# BRCM_V1.net
KiCad netlist of a schematic drawn in Altium Designer
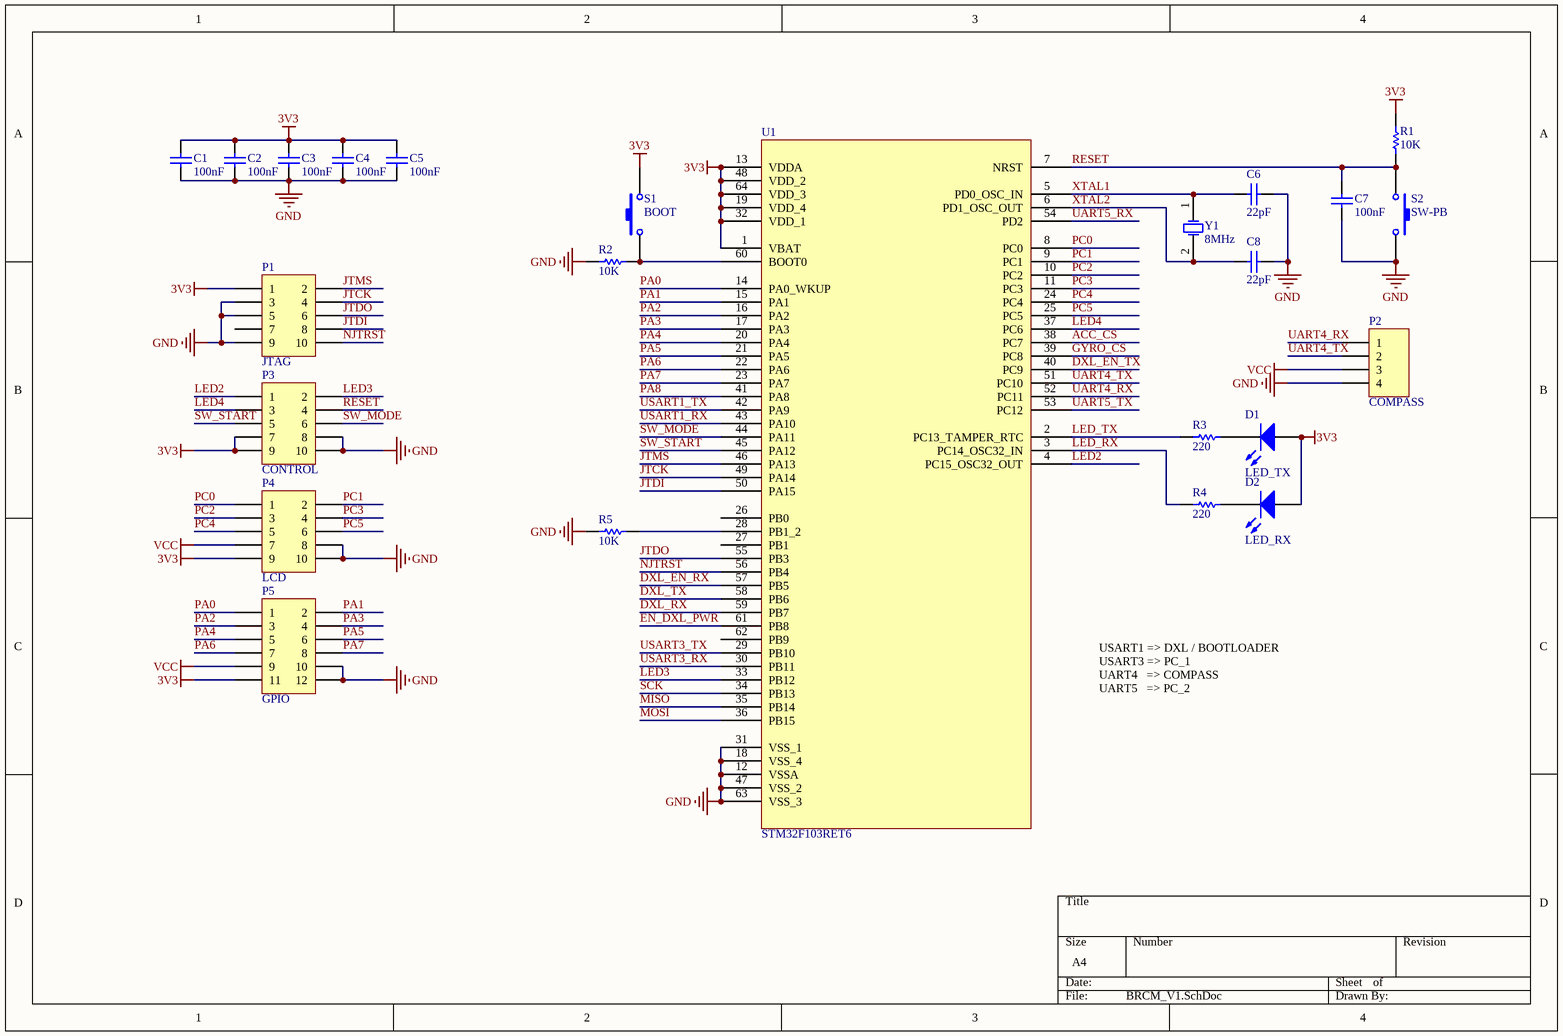
[diagram p0: BRCM_V1.SchDoc]

(export (version "E")
  (design (tool "Eeschema 10.0.6"))
  (components
    (comp (ref "C1")
      (value "100nF")
      (footprint "0603-CAP")
      (description "Capacitor")
      (fields (field (name "PUBLISHER") "Altium Limited"))
      (libsource (lib "BarelangRobotics") (part "Cap"))
    )
    (comp (ref "C2")
      (value "100nF")
      (footprint "0603-CAP")
      (description "Capacitor")
      (fields (field (name "PUBLISHER") "Altium Limited"))
      (libsource (lib "BarelangRobotics") (part "Cap"))
    )
    (comp (ref "C3")
      (value "100nF")
      (footprint "0603-CAP")
      (description "Capacitor")
      (fields (field (name "PUBLISHER") "Altium Limited"))
      (libsource (lib "BarelangRobotics") (part "Cap"))
    )
    (comp (ref "C4")
      (value "100nF")
      (footprint "0603-CAP")
      (description "Capacitor")
      (fields (field (name "PUBLISHER") "Altium Limited"))
      (libsource (lib "BarelangRobotics") (part "Cap"))
    )
    (comp (ref "C5")
      (value "100nF")
      (footprint "0603-CAP")
      (description "Capacitor")
      (fields (field (name "PUBLISHER") "Altium Limited"))
      (libsource (lib "BarelangRobotics") (part "Cap"))
    )
    (comp (ref "C6")
      (value "22pF")
      (footprint "0603-CAP")
      (description "Capacitor")
      (fields (field (name "PUBLISHER") "Altium Limited"))
      (libsource (lib "BarelangRobotics") (part "Cap"))
    )
    (comp (ref "C7")
      (value "100nF")
      (footprint "0603-CAP")
      (description "Capacitor")
      (fields (field (name "PUBLISHER") "Altium Limited"))
      (libsource (lib "BarelangRobotics") (part "Cap"))
    )
    (comp (ref "C8")
      (value "22pF")
      (footprint "0603-CAP")
      (description "Capacitor")
      (fields (field (name "PUBLISHER") "Altium Limited"))
      (libsource (lib "BarelangRobotics") (part "Cap"))
    )
    (comp (ref "D1")
      (value "LED_TX")
      (footprint "CHIPLED_0603")
      (description "Typical INFRARED GaAs LED")
      (fields (field (name "PUBLISHER") "Altium Limited"))
      (libsource (lib "BarelangRobotics") (part "LED"))
    )
    (comp (ref "D2")
      (value "LED_RX")
      (footprint "CHIPLED_0603")
      (description "Typical INFRARED GaAs LED")
      (fields (field (name "PUBLISHER") "Altium Limited"))
      (libsource (lib "BarelangRobotics") (part "LED"))
    )
    (comp (ref "P1")
      (value "JTAG")
      (footprint "HDR2X5")
      (description "Header, 5-Pin, Dual row")
      (fields (field (name "PUBLISHER") "Altium Limited"))
      (libsource (lib "BarelangRobotics") (part "Header 5X2"))
    )
    (comp (ref "P2")
      (value "COMPASS")
      (footprint "HDR1X4")
      (description "Header, 4-Pin")
      (fields (field (name "PUBLISHER") "Altium Limited"))
      (libsource (lib "BarelangRobotics") (part "Header 4"))
    )
    (comp (ref "P3")
      (value "CONTROL")
      (footprint "HDR2X5")
      (description "Header, 5-Pin, Dual row")
      (fields (field (name "PUBLISHER") "Altium Limited"))
      (libsource (lib "BarelangRobotics") (part "Header 5X2"))
    )
    (comp (ref "P4")
      (value "LCD")
      (footprint "HDR2X5")
      (description "Header, 5-Pin, Dual row")
      (fields (field (name "PUBLISHER") "Altium Limited"))
      (libsource (lib "BarelangRobotics") (part "Header 5X2"))
    )
    (comp (ref "P5")
      (value "GPIO")
      (footprint "HDR2X6")
      (description "Header, 6-Pin, Dual row")
      (fields (field (name "PUBLISHER") "Altium Limited"))
      (libsource (lib "BarelangRobotics") (part "Header 6X2"))
    )
    (comp (ref "R1")
      (value "10K")
      (footprint "0603-RES")
      (description "Resistor")
      (fields (field (name "PUBLISHER") "Altium Limited"))
      (libsource (lib "BarelangRobotics") (part "Res"))
    )
    (comp (ref "R2")
      (value "10K")
      (footprint "0603-RES")
      (description "Resistor")
      (fields (field (name "PUBLISHER") "Altium Limited"))
      (libsource (lib "BarelangRobotics") (part "Res"))
    )
    (comp (ref "R3")
      (value "220")
      (footprint "0603-RES")
      (description "Resistor")
      (fields (field (name "PUBLISHER") "Altium Limited"))
      (libsource (lib "BarelangRobotics") (part "Res"))
    )
    (comp (ref "R4")
      (value "220")
      (footprint "0603-RES")
      (description "Resistor")
      (fields (field (name "PUBLISHER") "Altium Limited"))
      (libsource (lib "BarelangRobotics") (part "Res"))
    )
    (comp (ref "R5")
      (value "10K")
      (footprint "0603-RES")
      (description "Resistor")
      (fields (field (name "PUBLISHER") "Altium Limited"))
      (libsource (lib "BarelangRobotics") (part "Res"))
    )
    (comp (ref "S1")
      (value "BOOT")
      (footprint "TACTILE-SWITCH-SMD")
      (description "Switch")
      (fields (field (name "PUBLISHER") "Altium Limited"))
      (libsource (lib "BarelangRobotics") (part "SW-PB"))
    )
    (comp (ref "S2")
      (value "SW-PB")
      (footprint "TACTILE-SWITCH-SMD")
      (description "Switch")
      (fields (field (name "PUBLISHER") "Altium Limited"))
      (libsource (lib "BarelangRobotics") (part "SW-PB"))
    )
    (comp (ref "U1")
      (value "STM32F103RET6")
      (footprint "QFP-64N")
      (libsource (lib "BarelangRobotics") (part "STM32F103RET6"))
    )
    (comp (ref "Y1")
      (value "8MHz")
      (footprint "HC49UP")
      (description "Crystal Oscillator")
      (fields (field (name "PUBLISHER") "Altium Limited"))
      (libsource (lib "BarelangRobotics") (part "XTAL"))
    )
  )
  (nets
    (net (code "1") (name "/ACC_CS") (class "Default")
      (node (ref "U1") (pin "38") (pinfunction "PC7_38") (pintype "passive"))
    )
    (net (code "2") (name "/DXL_EN_RX") (class "Default")
      (node (ref "U1") (pin "57") (pinfunction "PB5_57") (pintype "passive"))
    )
    (net (code "3") (name "/DXL_EN_TX") (class "Default")
      (node (ref "U1") (pin "40") (pinfunction "PC9_40") (pintype "passive"))
    )
    (net (code "4") (name "/DXL_RX") (class "Default")
      (node (ref "U1") (pin "59") (pinfunction "PB7_59") (pintype "passive"))
    )
    (net (code "5") (name "/DXL_TX") (class "Default")
      (node (ref "U1") (pin "58") (pinfunction "PB6_58") (pintype "passive"))
    )
    (net (code "6") (name "/EN_DXL_PWR") (class "Default")
      (node (ref "U1") (pin "61") (pinfunction "PB8_61") (pintype "passive"))
    )
    (net (code "7") (name "/GYRO_CS") (class "Default")
      (node (ref "U1") (pin "39") (pinfunction "PC8_39") (pintype "passive"))
    )
    (net (code "8") (name "/JTCK") (class "Default")
      (node (ref "P1") (pin "4") (pinfunction "4_4") (pintype "passive"))
      (node (ref "U1") (pin "49") (pinfunction "PA14_49") (pintype "passive"))
    )
    (net (code "9") (name "/JTDI") (class "Default")
      (node (ref "P1") (pin "8") (pinfunction "8_8") (pintype "passive"))
      (node (ref "U1") (pin "50") (pinfunction "PA15_50") (pintype "passive"))
    )
    (net (code "10") (name "/JTDO") (class "Default")
      (node (ref "P1") (pin "6") (pinfunction "6_6") (pintype "passive"))
      (node (ref "U1") (pin "55") (pinfunction "PB3_55") (pintype "passive"))
    )
    (net (code "11") (name "/JTMS") (class "Default")
      (node (ref "P1") (pin "2") (pinfunction "2_2") (pintype "passive"))
      (node (ref "U1") (pin "46") (pinfunction "PA13_46") (pintype "passive"))
    )
    (net (code "12") (name "/LED2") (class "Default")
      (node (ref "P3") (pin "1") (pinfunction "1_1") (pintype "passive"))
      (node (ref "U1") (pin "4") (pinfunction "PC15_OSC32_OUT_4") (pintype "passive"))
    )
    (net (code "13") (name "/LED3") (class "Default")
      (node (ref "P3") (pin "2") (pinfunction "2_2") (pintype "passive"))
      (node (ref "U1") (pin "33") (pinfunction "PB12_33") (pintype "passive"))
    )
    (net (code "14") (name "/LED4") (class "Default")
      (node (ref "P3") (pin "3") (pinfunction "3_3") (pintype "passive"))
      (node (ref "U1") (pin "37") (pinfunction "PC6_37") (pintype "passive"))
    )
    (net (code "15") (name "/LED_RX") (class "Default")
      (node (ref "R4") (pin "1") (pinfunction "1_1") (pintype "passive"))
      (node (ref "U1") (pin "3") (pinfunction "PC14_OSC32_IN_3") (pintype "passive"))
    )
    (net (code "16") (name "/LED_TX") (class "Default")
      (node (ref "R3") (pin "1") (pinfunction "1_1") (pintype "passive"))
      (node (ref "U1") (pin "2") (pinfunction "PC13_TAMPER_RTC_2") (pintype "passive"))
    )
    (net (code "17") (name "/MISO") (class "Default")
      (node (ref "U1") (pin "35") (pinfunction "PB14_35") (pintype "passive"))
    )
    (net (code "18") (name "/MOSI") (class "Default")
      (node (ref "U1") (pin "36") (pinfunction "PB15_36") (pintype "passive"))
    )
    (net (code "19") (name "/NJTRST") (class "Default")
      (node (ref "P1") (pin "10") (pinfunction "10_10") (pintype "passive"))
      (node (ref "U1") (pin "56") (pinfunction "PB4_56") (pintype "passive"))
    )
    (net (code "20") (name "/PA0") (class "Default")
      (node (ref "P5") (pin "1") (pinfunction "1_1") (pintype "passive"))
      (node (ref "U1") (pin "14") (pinfunction "PA0_WKUP_14") (pintype "passive"))
    )
    (net (code "21") (name "/PA1") (class "Default")
      (node (ref "P5") (pin "2") (pinfunction "2_2") (pintype "passive"))
      (node (ref "U1") (pin "15") (pinfunction "PA1_15") (pintype "passive"))
    )
    (net (code "22") (name "/PA2") (class "Default")
      (node (ref "P5") (pin "3") (pinfunction "3_3") (pintype "passive"))
      (node (ref "U1") (pin "16") (pinfunction "PA2_16") (pintype "passive"))
    )
    (net (code "23") (name "/PA3") (class "Default")
      (node (ref "P5") (pin "4") (pinfunction "4_4") (pintype "passive"))
      (node (ref "U1") (pin "17") (pinfunction "PA3_17") (pintype "passive"))
    )
    (net (code "24") (name "/PA4") (class "Default")
      (node (ref "P5") (pin "5") (pinfunction "5_5") (pintype "passive"))
      (node (ref "U1") (pin "20") (pinfunction "PA4_20") (pintype "passive"))
    )
    (net (code "25") (name "/PA5") (class "Default")
      (node (ref "P5") (pin "6") (pinfunction "6_6") (pintype "passive"))
      (node (ref "U1") (pin "21") (pinfunction "PA5_21") (pintype "passive"))
    )
    (net (code "26") (name "/PA6") (class "Default")
      (node (ref "P5") (pin "7") (pinfunction "7_7") (pintype "passive"))
      (node (ref "U1") (pin "22") (pinfunction "PA6_22") (pintype "passive"))
    )
    (net (code "27") (name "/PA7") (class "Default")
      (node (ref "P5") (pin "8") (pinfunction "8_8") (pintype "passive"))
      (node (ref "U1") (pin "23") (pinfunction "PA7_23") (pintype "passive"))
    )
    (net (code "28") (name "/PA8") (class "Default")
      (node (ref "U1") (pin "41") (pinfunction "PA8_41") (pintype "passive"))
    )
    (net (code "29") (name "/PC0") (class "Default")
      (node (ref "P4") (pin "1") (pinfunction "1_1") (pintype "passive"))
      (node (ref "U1") (pin "8") (pinfunction "PC0_8") (pintype "passive"))
    )
    (net (code "30") (name "/PC1") (class "Default")
      (node (ref "P4") (pin "2") (pinfunction "2_2") (pintype "passive"))
      (node (ref "U1") (pin "9") (pinfunction "PC1_9") (pintype "passive"))
    )
    (net (code "31") (name "/PC2") (class "Default")
      (node (ref "P4") (pin "3") (pinfunction "3_3") (pintype "passive"))
      (node (ref "U1") (pin "10") (pinfunction "PC2_10") (pintype "passive"))
    )
    (net (code "32") (name "/PC3") (class "Default")
      (node (ref "P4") (pin "4") (pinfunction "4_4") (pintype "passive"))
      (node (ref "U1") (pin "11") (pinfunction "PC3_11") (pintype "passive"))
    )
    (net (code "33") (name "/PC4") (class "Default")
      (node (ref "P4") (pin "5") (pinfunction "5_5") (pintype "passive"))
      (node (ref "U1") (pin "24") (pinfunction "PC4_24") (pintype "passive"))
    )
    (net (code "34") (name "/PC5") (class "Default")
      (node (ref "P4") (pin "6") (pinfunction "6_6") (pintype "passive"))
      (node (ref "U1") (pin "25") (pinfunction "PC5_25") (pintype "passive"))
    )
    (net (code "35") (name "/RESET") (class "Default")
      (node (ref "C7") (pin "2") (pinfunction "2_2") (pintype "passive"))
      (node (ref "P3") (pin "4") (pinfunction "4_4") (pintype "passive"))
      (node (ref "R1") (pin "1") (pinfunction "1_1") (pintype "passive"))
      (node (ref "S2") (pin "1") (pinfunction "1_1") (pintype "passive"))
      (node (ref "U1") (pin "7") (pinfunction "NRST_7") (pintype "passive"))
    )
    (net (code "36") (name "/SCK") (class "Default")
      (node (ref "U1") (pin "34") (pinfunction "PB13_34") (pintype "passive"))
    )
    (net (code "37") (name "/SW_MODE") (class "Default")
      (node (ref "P3") (pin "6") (pinfunction "6_6") (pintype "passive"))
      (node (ref "U1") (pin "44") (pinfunction "PA11_44") (pintype "passive"))
    )
    (net (code "38") (name "/SW_START") (class "Default")
      (node (ref "P3") (pin "5") (pinfunction "5_5") (pintype "passive"))
      (node (ref "U1") (pin "45") (pinfunction "PA12_45") (pintype "passive"))
    )
    (net (code "39") (name "/UART4_RX") (class "Default")
      (node (ref "P2") (pin "1") (pinfunction "1_1") (pintype "passive"))
      (node (ref "U1") (pin "52") (pinfunction "PC11_52") (pintype "passive"))
    )
    (net (code "40") (name "/UART4_TX") (class "Default")
      (node (ref "P2") (pin "2") (pinfunction "2_2") (pintype "passive"))
      (node (ref "U1") (pin "51") (pinfunction "PC10_51") (pintype "passive"))
    )
    (net (code "41") (name "/UART5_RX") (class "Default")
      (node (ref "U1") (pin "54") (pinfunction "PD2_54") (pintype "passive"))
    )
    (net (code "42") (name "/UART5_TX") (class "Default")
      (node (ref "U1") (pin "53") (pinfunction "PC12_53") (pintype "passive"))
    )
    (net (code "43") (name "/USART1_RX") (class "Default")
      (node (ref "U1") (pin "43") (pinfunction "PA10_43") (pintype "passive"))
    )
    (net (code "44") (name "/USART1_TX") (class "Default")
      (node (ref "U1") (pin "42") (pinfunction "PA9_42") (pintype "passive"))
    )
    (net (code "45") (name "/USART3_RX") (class "Default")
      (node (ref "U1") (pin "30") (pinfunction "PB11_30") (pintype "passive"))
    )
    (net (code "46") (name "/USART3_TX") (class "Default")
      (node (ref "U1") (pin "29") (pinfunction "PB10_29") (pintype "passive"))
    )
    (net (code "47") (name "/XTAL1") (class "Default")
      (node (ref "C6") (pin "2") (pinfunction "2_2") (pintype "passive"))
      (node (ref "U1") (pin "5") (pinfunction "PD0_OSC_IN_5") (pintype "passive"))
      (node (ref "Y1") (pin "1") (pinfunction "OSC1_1") (pintype "passive"))
    )
    (net (code "48") (name "/XTAL2") (class "Default")
      (node (ref "C8") (pin "2") (pinfunction "2_2") (pintype "passive"))
      (node (ref "U1") (pin "6") (pinfunction "PD1_OSC_OUT_6") (pintype "passive"))
      (node (ref "Y1") (pin "2") (pinfunction "OSC2_2") (pintype "passive"))
    )
    (net (code "49") (name "3V3") (class "Default")
      (node (ref "C1") (pin "2") (pinfunction "2_2") (pintype "passive"))
      (node (ref "C2") (pin "2") (pinfunction "2_2") (pintype "passive"))
      (node (ref "C3") (pin "2") (pinfunction "2_2") (pintype "passive"))
      (node (ref "C4") (pin "2") (pinfunction "2_2") (pintype "passive"))
      (node (ref "C5") (pin "2") (pinfunction "2_2") (pintype "passive"))
      (node (ref "D1") (pin "1") (pinfunction "A_1") (pintype "passive"))
      (node (ref "D2") (pin "1") (pinfunction "A_1") (pintype "passive"))
      (node (ref "P1") (pin "1") (pinfunction "1_1") (pintype "passive"))
      (node (ref "P3") (pin "7") (pinfunction "7_7") (pintype "passive"))
      (node (ref "P3") (pin "9") (pinfunction "9_9") (pintype "passive"))
      (node (ref "P4") (pin "9") (pinfunction "9_9") (pintype "passive"))
      (node (ref "P5") (pin "11") (pinfunction "11_11") (pintype "passive"))
      (node (ref "R1") (pin "2") (pinfunction "2_2") (pintype "passive"))
      (node (ref "S1") (pin "3") (pinfunction "3_3") (pintype "passive"))
      (node (ref "U1") (pin "1") (pinfunction "VBAT_1") (pintype "passive"))
      (node (ref "U1") (pin "13") (pinfunction "VDDA_13") (pintype "passive"))
      (node (ref "U1") (pin "19") (pinfunction "VDD_4_19") (pintype "passive"))
      (node (ref "U1") (pin "32") (pinfunction "VDD_1_32") (pintype "passive"))
      (node (ref "U1") (pin "48") (pinfunction "VDD_2_48") (pintype "passive"))
      (node (ref "U1") (pin "64") (pinfunction "VDD_3_64") (pintype "passive"))
    )
    (net (code "50") (name "GND") (class "Default")
      (node (ref "C1") (pin "1") (pinfunction "1_1") (pintype "passive"))
      (node (ref "C2") (pin "1") (pinfunction "1_1") (pintype "passive"))
      (node (ref "C3") (pin "1") (pinfunction "1_1") (pintype "passive"))
      (node (ref "C4") (pin "1") (pinfunction "1_1") (pintype "passive"))
      (node (ref "C5") (pin "1") (pinfunction "1_1") (pintype "passive"))
      (node (ref "C6") (pin "1") (pinfunction "1_1") (pintype "passive"))
      (node (ref "C7") (pin "1") (pinfunction "1_1") (pintype "passive"))
      (node (ref "C8") (pin "1") (pinfunction "1_1") (pintype "passive"))
      (node (ref "P1") (pin "3") (pinfunction "3_3") (pintype "passive"))
      (node (ref "P1") (pin "5") (pinfunction "5_5") (pintype "passive"))
      (node (ref "P1") (pin "9") (pinfunction "9_9") (pintype "passive"))
      (node (ref "P2") (pin "4") (pinfunction "4_4") (pintype "passive"))
      (node (ref "P3") (pin "10") (pinfunction "10_10") (pintype "passive"))
      (node (ref "P3") (pin "8") (pinfunction "8_8") (pintype "passive"))
      (node (ref "P4") (pin "10") (pinfunction "10_10") (pintype "passive"))
      (node (ref "P4") (pin "8") (pinfunction "8_8") (pintype "passive"))
      (node (ref "P5") (pin "10") (pinfunction "10_10") (pintype "passive"))
      (node (ref "P5") (pin "12") (pinfunction "12_12") (pintype "passive"))
      (node (ref "R2") (pin "1") (pinfunction "1_1") (pintype "passive"))
      (node (ref "R5") (pin "1") (pinfunction "1_1") (pintype "passive"))
      (node (ref "S2") (pin "3") (pinfunction "3_3") (pintype "passive"))
      (node (ref "U1") (pin "12") (pinfunction "VSSA_12") (pintype "passive"))
      (node (ref "U1") (pin "18") (pinfunction "VSS_4_18") (pintype "passive"))
      (node (ref "U1") (pin "31") (pinfunction "VSS_1_31") (pintype "passive"))
      (node (ref "U1") (pin "47") (pinfunction "VSS_2_47") (pintype "passive"))
      (node (ref "U1") (pin "63") (pinfunction "VSS_3_63") (pintype "passive"))
    )
    (net (code "51") (name "Net-(D1-K)") (class "Default")
      (node (ref "D1") (pin "2") (pinfunction "K_2") (pintype "passive"))
      (node (ref "R3") (pin "2") (pinfunction "2_2") (pintype "passive"))
    )
    (net (code "52") (name "Net-(D2-K)") (class "Default")
      (node (ref "D2") (pin "2") (pinfunction "K_2") (pintype "passive"))
      (node (ref "R4") (pin "2") (pinfunction "2_2") (pintype "passive"))
    )
    (net (code "53") (name "Net-(U1-BOOT0)") (class "Default")
      (node (ref "R2") (pin "2") (pinfunction "2_2") (pintype "passive"))
      (node (ref "S1") (pin "1") (pinfunction "1_1") (pintype "passive"))
      (node (ref "U1") (pin "60") (pinfunction "BOOT0_60") (pintype "passive"))
    )
    (net (code "54") (name "Net-(U1-PB1_2)") (class "Default")
      (node (ref "R5") (pin "2") (pinfunction "2_2") (pintype "passive"))
      (node (ref "U1") (pin "28") (pinfunction "PB1_2_28") (pintype "passive"))
    )
    (net (code "55") (name "VCC") (class "Default")
      (node (ref "P2") (pin "3") (pinfunction "3_3") (pintype "passive"))
      (node (ref "P4") (pin "7") (pinfunction "7_7") (pintype "passive"))
      (node (ref "P5") (pin "9") (pinfunction "9_9") (pintype "passive"))
    )
    (net (code "56") (name "unconnected-(P1-Pad7)") (class "Default")
      (node (ref "P1") (pin "7") (pinfunction "7_7") (pintype "passive"))
    )
    (net (code "57") (name "unconnected-(U1-PB0-Pad26)") (class "Default")
      (node (ref "U1") (pin "26") (pinfunction "PB0_26") (pintype "passive"))
    )
    (net (code "58") (name "unconnected-(U1-PB1-Pad27)") (class "Default")
      (node (ref "U1") (pin "27") (pinfunction "PB1_27") (pintype "passive"))
    )
    (net (code "59") (name "unconnected-(U1-PB9-Pad62)") (class "Default")
      (node (ref "U1") (pin "62") (pinfunction "PB9_62") (pintype "passive"))
    )
  )
)
